# WiFi_Interface.net
KiCad netlist of a schematic drawn in Altium Designer
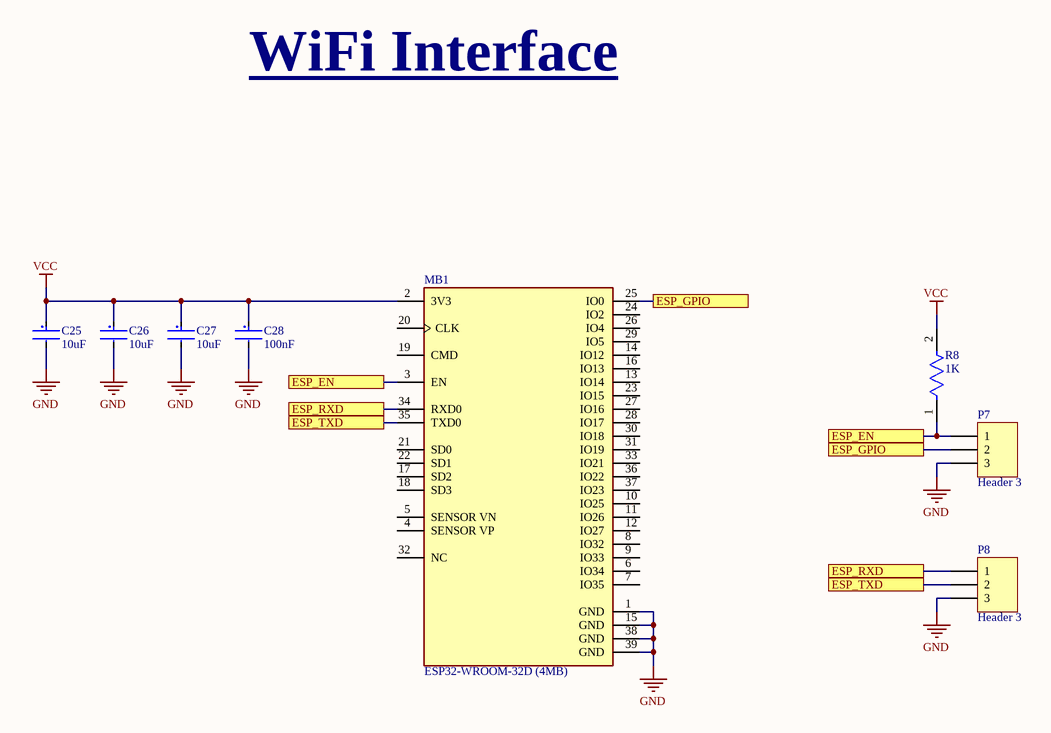
[diagram p0: WiFi_Interface.SchDoc]

(export (version "E")
  (design (tool "Eeschema 10.0.6"))
  (components
    (comp (ref "C25")
      (value "10uF")
      (footprint "Samsung_CL31_IPC_A_1206")
      (description "CAP CER 10UF 6.3V X5R 1206, ±10% 6.3V Ceramic Capacitor X5R 1206 (3216 Metric)")
      (libsource (lib "DMD_Card") (part "CL31A106KQHNNWE"))
    )
    (comp (ref "C26")
      (value "10uF")
      (footprint "Samsung_CL31_IPC_A_1206")
      (description "CAP CER 10UF 6.3V X5R 1206, ±10% 6.3V Ceramic Capacitor X5R 1206 (3216 Metric)")
      (libsource (lib "DMD_Card") (part "CL31A106KQHNNWE"))
    )
    (comp (ref "C27")
      (value "10uF")
      (footprint "Samsung_CL31_IPC_A_1206")
      (description "CAP CER 10UF 6.3V X5R 1206, ±10% 6.3V Ceramic Capacitor X5R 1206 (3216 Metric)")
      (libsource (lib "DMD_Card") (part "CL31A106KQHNNWE"))
    )
    (comp (ref "C28")
      (value "100nF")
      (footprint "Samsung_CL31_IPC_A_1206")
      (description "CAP CER 0.1UF 50V X7R 1206, ±10% 50V Ceramic Capacitor X7R 1206 (3216 Metric)")
      (libsource (lib "DMD_Card") (part "CL31B104KBCNFNC"))
    )
    (comp (ref "MB1")
      (value "ESP32-WROOM-32D (4MB)")
      (footprint "Espressif_Systems_0_MFG")
      (fields
        (field (name "MANUFACTURER") "Espressif Systems")
        (field (name "MANUFACTURER PART NUMBER") "ESP32-WROOM-32D(4MBHIGHTEMP)")
      )
      (libsource (lib "DMD_Card") (part "ESP32-WROOM-32D(4MBHIGHTEMP)"))
    )
    (comp (ref "P7")
      (value "Header 3")
      (footprint "HDR1X3")
      (description "Header, 3-Pin")
      (fields (field (name "PUBLISHER") "Altium Limited"))
      (libsource (lib "Miscellaneous Connectors") (part "Header 3"))
    )
    (comp (ref "P8")
      (value "Header 3")
      (footprint "HDR1X3")
      (description "Header, 3-Pin")
      (fields (field (name "PUBLISHER") "Altium Limited"))
      (libsource (lib "Miscellaneous Connectors") (part "Header 3"))
    )
    (comp (ref "R8")
      (value "1K")
      (footprint "YAGEO_RC1206-0_65_IPC_A")
      (description "1 ±5% 0.25W, 1/4W Chip Resistor 1206 (3216 Metric) Moisture Resistant Thick Film")
      (libsource (lib "DMD_Card") (part "RC1206JR-071KL"))
    )
  )
  (nets
    (net (code "1") (name "/ESP_EN") (class "Default")
      (node (ref "MB1") (pin "3") (pinfunction "EN_3") (pintype "passive"))
      (node (ref "P7") (pin "1") (pinfunction "1_1") (pintype "passive"))
      (node (ref "R8") (pin "1") (pinfunction "1_1") (pintype "passive"))
    )
    (net (code "2") (name "/ESP_GPIO") (class "Default")
      (node (ref "MB1") (pin "25") (pinfunction "IO0_25") (pintype "passive"))
      (node (ref "P7") (pin "2") (pinfunction "2_2") (pintype "passive"))
    )
    (net (code "3") (name "/ESP_RXD") (class "Default")
      (node (ref "MB1") (pin "34") (pinfunction "RXD0_34") (pintype "passive"))
      (node (ref "P8") (pin "1") (pinfunction "1_1") (pintype "passive"))
    )
    (net (code "4") (name "/ESP_TXD") (class "Default")
      (node (ref "MB1") (pin "35") (pinfunction "TXD0_35") (pintype "passive"))
      (node (ref "P8") (pin "2") (pinfunction "2_2") (pintype "passive"))
    )
    (net (code "5") (name "GND") (class "Default")
      (node (ref "C25") (pin "2") (pinfunction "2_2") (pintype "passive"))
      (node (ref "C26") (pin "2") (pinfunction "2_2") (pintype "passive"))
      (node (ref "C27") (pin "2") (pinfunction "2_2") (pintype "passive"))
      (node (ref "C28") (pin "2") (pinfunction "2_2") (pintype "passive"))
      (node (ref "MB1") (pin "1") (pinfunction "GND_1") (pintype "passive"))
      (node (ref "MB1") (pin "15") (pinfunction "GND_15") (pintype "passive"))
      (node (ref "MB1") (pin "38") (pinfunction "GND_38") (pintype "passive"))
      (node (ref "MB1") (pin "39") (pinfunction "GND_39") (pintype "passive"))
      (node (ref "P7") (pin "3") (pinfunction "3_3") (pintype "passive"))
      (node (ref "P8") (pin "3") (pinfunction "3_3") (pintype "passive"))
    )
    (net (code "6") (name "VCC") (class "Default")
      (node (ref "C25") (pin "1") (pinfunction "1_1") (pintype "passive"))
      (node (ref "C26") (pin "1") (pinfunction "1_1") (pintype "passive"))
      (node (ref "C27") (pin "1") (pinfunction "1_1") (pintype "passive"))
      (node (ref "C28") (pin "1") (pinfunction "1_1") (pintype "passive"))
      (node (ref "MB1") (pin "2") (pinfunction "3V3_2") (pintype "passive"))
      (node (ref "R8") (pin "2") (pinfunction "2_2") (pintype "passive"))
    )
    (net (code "7") (name "unconnected-(MB1-CLK-Pad20)") (class "Default")
      (node (ref "MB1") (pin "20") (pinfunction "CLK_20") (pintype "passive"))
    )
    (net (code "8") (name "unconnected-(MB1-CMD-Pad19)") (class "Default")
      (node (ref "MB1") (pin "19") (pinfunction "CMD_19") (pintype "passive"))
    )
    (net (code "9") (name "unconnected-(MB1-IO2-Pad24)") (class "Default")
      (node (ref "MB1") (pin "24") (pinfunction "IO2_24") (pintype "passive"))
    )
    (net (code "10") (name "unconnected-(MB1-IO4-Pad26)") (class "Default")
      (node (ref "MB1") (pin "26") (pinfunction "IO4_26") (pintype "passive"))
    )
    (net (code "11") (name "unconnected-(MB1-IO5-Pad29)") (class "Default")
      (node (ref "MB1") (pin "29") (pinfunction "IO5_29") (pintype "passive"))
    )
    (net (code "12") (name "unconnected-(MB1-IO12-Pad14)") (class "Default")
      (node (ref "MB1") (pin "14") (pinfunction "IO12_14") (pintype "passive"))
    )
    (net (code "13") (name "unconnected-(MB1-IO13-Pad16)") (class "Default")
      (node (ref "MB1") (pin "16") (pinfunction "IO13_16") (pintype "passive"))
    )
    (net (code "14") (name "unconnected-(MB1-IO14-Pad13)") (class "Default")
      (node (ref "MB1") (pin "13") (pinfunction "IO14_13") (pintype "passive"))
    )
    (net (code "15") (name "unconnected-(MB1-IO15-Pad23)") (class "Default")
      (node (ref "MB1") (pin "23") (pinfunction "IO15_23") (pintype "passive"))
    )
    (net (code "16") (name "unconnected-(MB1-IO16-Pad27)") (class "Default")
      (node (ref "MB1") (pin "27") (pinfunction "IO16_27") (pintype "passive"))
    )
    (net (code "17") (name "unconnected-(MB1-IO17-Pad28)") (class "Default")
      (node (ref "MB1") (pin "28") (pinfunction "IO17_28") (pintype "passive"))
    )
    (net (code "18") (name "unconnected-(MB1-IO18-Pad30)") (class "Default")
      (node (ref "MB1") (pin "30") (pinfunction "IO18_30") (pintype "passive"))
    )
    (net (code "19") (name "unconnected-(MB1-IO19-Pad31)") (class "Default")
      (node (ref "MB1") (pin "31") (pinfunction "IO19_31") (pintype "passive"))
    )
    (net (code "20") (name "unconnected-(MB1-IO21-Pad33)") (class "Default")
      (node (ref "MB1") (pin "33") (pinfunction "IO21_33") (pintype "passive"))
    )
    (net (code "21") (name "unconnected-(MB1-IO22-Pad36)") (class "Default")
      (node (ref "MB1") (pin "36") (pinfunction "IO22_36") (pintype "passive"))
    )
    (net (code "22") (name "unconnected-(MB1-IO23-Pad37)") (class "Default")
      (node (ref "MB1") (pin "37") (pinfunction "IO23_37") (pintype "passive"))
    )
    (net (code "23") (name "unconnected-(MB1-IO25-Pad10)") (class "Default")
      (node (ref "MB1") (pin "10") (pinfunction "IO25_10") (pintype "passive"))
    )
    (net (code "24") (name "unconnected-(MB1-IO26-Pad11)") (class "Default")
      (node (ref "MB1") (pin "11") (pinfunction "IO26_11") (pintype "passive"))
    )
    (net (code "25") (name "unconnected-(MB1-IO27-Pad12)") (class "Default")
      (node (ref "MB1") (pin "12") (pinfunction "IO27_12") (pintype "passive"))
    )
    (net (code "26") (name "unconnected-(MB1-IO32-Pad8)") (class "Default")
      (node (ref "MB1") (pin "8") (pinfunction "IO32_8") (pintype "passive"))
    )
    (net (code "27") (name "unconnected-(MB1-IO33-Pad9)") (class "Default")
      (node (ref "MB1") (pin "9") (pinfunction "IO33_9") (pintype "passive"))
    )
    (net (code "28") (name "unconnected-(MB1-IO34-Pad6)") (class "Default")
      (node (ref "MB1") (pin "6") (pinfunction "IO34_6") (pintype "passive"))
    )
    (net (code "29") (name "unconnected-(MB1-IO35-Pad7)") (class "Default")
      (node (ref "MB1") (pin "7") (pinfunction "IO35_7") (pintype "passive"))
    )
    (net (code "30") (name "unconnected-(MB1-NC-Pad32)") (class "Default")
      (node (ref "MB1") (pin "32") (pinfunction "NC_32") (pintype "passive"))
    )
    (net (code "31") (name "unconnected-(MB1-SD0-Pad21)") (class "Default")
      (node (ref "MB1") (pin "21") (pinfunction "SD0_21") (pintype "passive"))
    )
    (net (code "32") (name "unconnected-(MB1-SD1-Pad22)") (class "Default")
      (node (ref "MB1") (pin "22") (pinfunction "SD1_22") (pintype "passive"))
    )
    (net (code "33") (name "unconnected-(MB1-SD2-Pad17)") (class "Default")
      (node (ref "MB1") (pin "17") (pinfunction "SD2_17") (pintype "passive"))
    )
    (net (code "34") (name "unconnected-(MB1-SD3-Pad18)") (class "Default")
      (node (ref "MB1") (pin "18") (pinfunction "SD3_18") (pintype "passive"))
    )
    (net (code "35") (name "unconnected-(MB1-SENSOR_VN-Pad5)") (class "Default")
      (node (ref "MB1") (pin "5") (pinfunction "SENSOR_VN_5") (pintype "passive"))
    )
    (net (code "36") (name "unconnected-(MB1-SENSOR_VP-Pad4)") (class "Default")
      (node (ref "MB1") (pin "4") (pinfunction "SENSOR_VP_4") (pintype "passive"))
    )
  )
)
